# SL_LCD_SW_LED_2E.net
KiCad netlist of a schematic drawn in Altium Designer
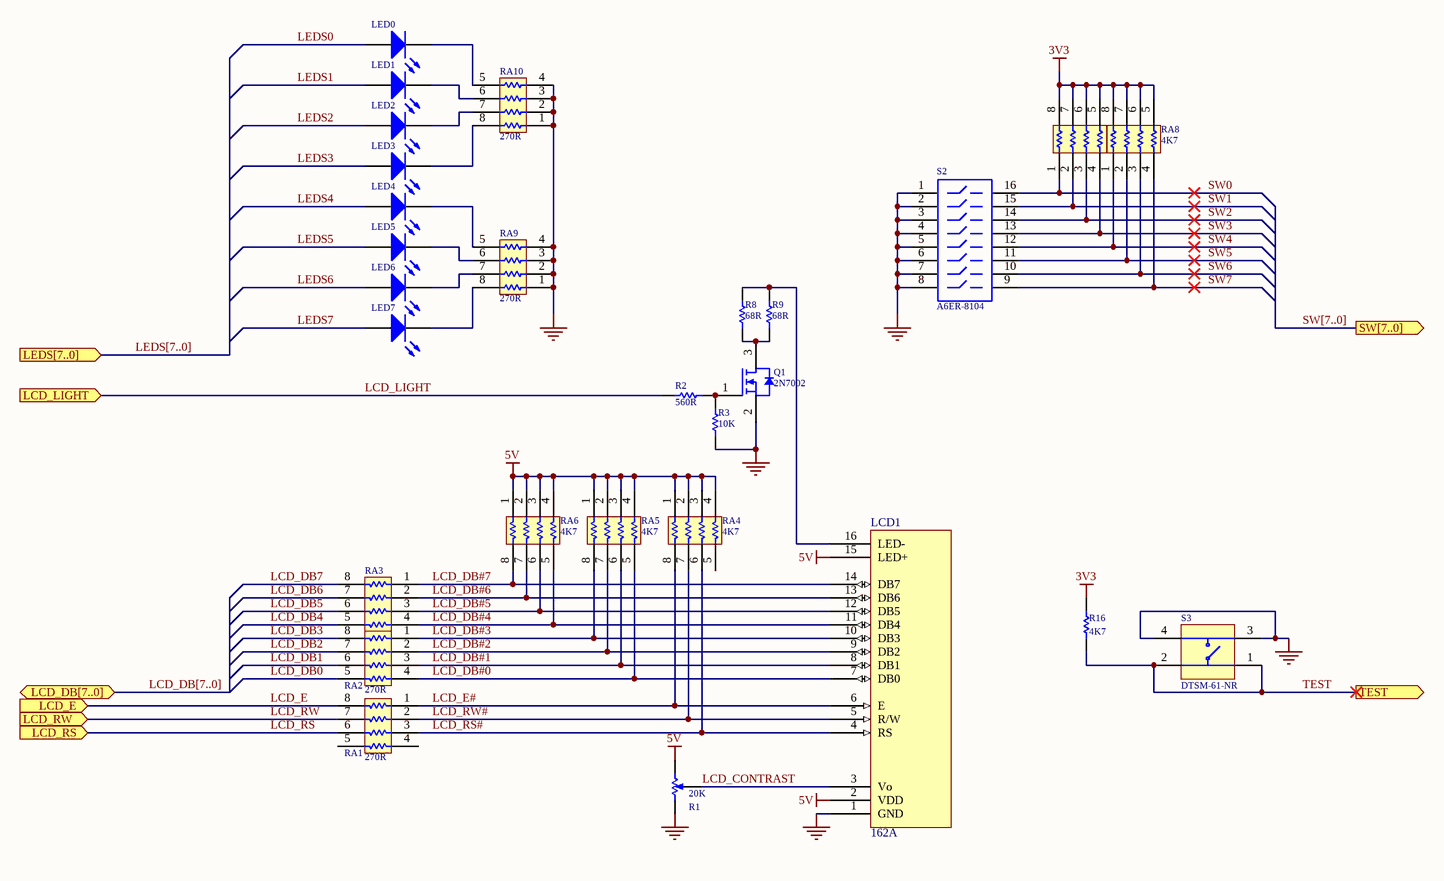
[diagram p0: SL_LCD_SW_LED_2E.SchDoc]

(export (version "E")
  (design (tool "Eeschema 10.0.6"))
  (components
    (comp (ref "LCD1")
      (value "162A")
      (footprint "Spirit_Level_Project:162A")
      (description "16 char * 2 line LCD character display with b/light")
      (libsource (lib "SpiritLevel_2E") (part "162A"))
    )
    (comp (ref "LED0")
      (value "HSMH-C170")
      (footprint "Spirit_Level_Project:SMD _LED")
      (description "Typical RED GaAs SMD LED Agilent make")
      (libsource (lib "SpiritLevel_2E") (part "HSMX-C670"))
    )
    (comp (ref "LED1")
      (value "HSMH-C170")
      (footprint "Spirit_Level_Project:SMD _LED")
      (description "Typical RED GaAs SMD LED Agilent make")
      (libsource (lib "SpiritLevel_2E") (part "HSMX-C670"))
    )
    (comp (ref "LED2")
      (value "HSMH-C170")
      (footprint "Spirit_Level_Project:SMD _LED")
      (description "Typical RED GaAs SMD LED Agilent make")
      (libsource (lib "SpiritLevel_2E") (part "HSMX-C670"))
    )
    (comp (ref "LED3")
      (value "HSMH-C170")
      (footprint "Spirit_Level_Project:SMD _LED")
      (description "Typical RED GaAs SMD LED Agilent make")
      (libsource (lib "SpiritLevel_2E") (part "HSMX-C670"))
    )
    (comp (ref "LED4")
      (value "HSMH-C170")
      (footprint "Spirit_Level_Project:SMD _LED")
      (description "Typical RED GaAs SMD LED Agilent make")
      (libsource (lib "SpiritLevel_2E") (part "HSMX-C670"))
    )
    (comp (ref "LED5")
      (value "HSMH-C170")
      (footprint "Spirit_Level_Project:SMD _LED")
      (description "Typical RED GaAs SMD LED Agilent make")
      (libsource (lib "SpiritLevel_2E") (part "HSMX-C670"))
    )
    (comp (ref "LED6")
      (value "HSMH-C170")
      (footprint "Spirit_Level_Project:SMD _LED")
      (description "Typical RED GaAs SMD LED Agilent make")
      (libsource (lib "SpiritLevel_2E") (part "HSMX-C670"))
    )
    (comp (ref "LED7")
      (value "HSMH-C170")
      (footprint "Spirit_Level_Project:SMD _LED")
      (description "Typical RED GaAs SMD LED Agilent make")
      (libsource (lib "SpiritLevel_2E") (part "HSMX-C670"))
    )
    (comp (ref "Q1")
      (value "2N7002")
      (footprint "Spirit_Level_Project:SO-G3")
      (description "N Channel Mosfet")
      (libsource (lib "SpiritLevel_2E") (part "2N7002"))
    )
    (comp (ref "R1")
      (value "20K")
      (footprint "Spirit_Level_Project:POT4MM-2")
      (description "Square Trimming Potentiometer")
      (libsource (lib "SpiritLevel_2E") (part "RPot SM"))
    )
    (comp (ref "R2")
      (value "560R")
      (footprint "CC2012-0805")
      (description "Resistor")
      (libsource (lib "SpiritLevel_2E") (part "RES"))
    )
    (comp (ref "R3")
      (value "10K")
      (footprint "CC2012-0805")
      (description "Resistor")
      (libsource (lib "SpiritLevel_2E") (part "RES"))
    )
    (comp (ref "R8")
      (value "68R")
      (footprint "CC2012-0805")
      (description "Resistor")
      (libsource (lib "") (part "RES_1"))
    )
    (comp (ref "R9")
      (value "68R")
      (footprint "CC2012-0805")
      (description "Resistor")
      (libsource (lib "") (part "RES_1"))
    )
    (comp (ref "R16")
      (value "4K7")
      (footprint "CC2012-0805")
      (description "Resistor")
      (libsource (lib "SpiritLevel_2E") (part "RES"))
    )
    (comp (ref "RA1")
      (value "270R")
      (footprint "Spirit_Level_Project:MNR34")
      (description "3216x4 Resistor Array")
      (libsource (lib "SpiritLevel_2E") (part "MNR34"))
    )
    (comp (ref "RA2")
      (value "270R")
      (footprint "Spirit_Level_Project:MNR34")
      (description "3216x4 Resistor Array")
      (libsource (lib "SpiritLevel_2E") (part "MNR34"))
    )
    (comp (ref "RA3")
      (value "270R")
      (footprint "Spirit_Level_Project:MNR34")
      (description "3216x4 Resistor Array")
      (libsource (lib "SpiritLevel_2E") (part "MNR34"))
    )
    (comp (ref "RA4")
      (value "4K7")
      (footprint "Spirit_Level_Project:MNR34T")
      (description "3216x4 Resistor Array")
      (libsource (lib "") (part "MNR34_1"))
    )
    (comp (ref "RA5")
      (value "4K7")
      (footprint "Spirit_Level_Project:MNR34T")
      (description "3216x4 Resistor Array")
      (libsource (lib "") (part "MNR34_1"))
    )
    (comp (ref "RA6")
      (value "4K7")
      (footprint "Spirit_Level_Project:MNR34T")
      (description "3216x4 Resistor Array")
      (libsource (lib "") (part "MNR34_1"))
    )
    (comp (ref "RA7")
      (value "4K7")
      (footprint "Spirit_Level_Project:MNR34T")
      (description "3216x4 Resistor Array")
      (libsource (lib "") (part "MNR34_2"))
    )
    (comp (ref "RA8")
      (value "4K7")
      (footprint "Spirit_Level_Project:MNR34T")
      (description "3216x4 Resistor Array")
      (libsource (lib "") (part "MNR34_2"))
    )
    (comp (ref "RA9")
      (value "270R")
      (footprint "Spirit_Level_Project:MNR34T")
      (description "3216x4 Resistor Array")
      (libsource (lib "") (part "MNR34_3"))
    )
    (comp (ref "RA10")
      (value "270R")
      (footprint "Spirit_Level_Project:MNR34T")
      (description "3216x4 Resistor Array")
      (libsource (lib "") (part "MNR34_3"))
    )
    (comp (ref "S2")
      (value "A6ER-8104")
      (footprint "Spirit_Level_Project:DIP-16-KEY")
      (description "DIP Switch Side actuator long liver Piano Key")
      (libsource (lib "SpiritLevel_2E") (part "A6ER-8104"))
    )
    (comp (ref "S3")
      (value "DTSM-61-NR")
      (footprint "Spirit_Level_Project:B3FS_SWITCH")
      (description "SPNA SMD Keyboard Switch")
      (libsource (lib "SpiritLevel_2E") (part "B3FS"))
    )
  )
  (nets
    (net (code "1") (name "/LCD_CONTRAST") (class "Default")
      (node (ref "LCD1") (pin "3") (pinfunction "Vo_3") (pintype "tri_state"))
      (node (ref "R1") (pin "W") (pintype "passive"))
    )
    (net (code "2") (name "/LCD_DB#0") (class "Default")
      (node (ref "LCD1") (pin "7") (pinfunction "DB0_7") (pintype "bidirectional"))
      (node (ref "RA2") (pin "4") (pintype "passive"))
      (node (ref "RA5") (pin "5") (pintype "passive"))
    )
    (net (code "3") (name "/LCD_DB#1") (class "Default")
      (node (ref "LCD1") (pin "8") (pinfunction "DB1_8") (pintype "bidirectional"))
      (node (ref "RA2") (pin "3") (pintype "passive"))
      (node (ref "RA5") (pin "6") (pintype "passive"))
    )
    (net (code "4") (name "/LCD_DB#2") (class "Default")
      (node (ref "LCD1") (pin "9") (pinfunction "DB2_9") (pintype "bidirectional"))
      (node (ref "RA2") (pin "2") (pintype "passive"))
      (node (ref "RA5") (pin "7") (pintype "passive"))
    )
    (net (code "5") (name "/LCD_DB#3") (class "Default")
      (node (ref "LCD1") (pin "10") (pinfunction "DB3_10") (pintype "bidirectional"))
      (node (ref "RA2") (pin "1") (pintype "passive"))
      (node (ref "RA5") (pin "8") (pintype "passive"))
    )
    (net (code "6") (name "/LCD_DB#4") (class "Default")
      (node (ref "LCD1") (pin "11") (pinfunction "DB4_11") (pintype "bidirectional"))
      (node (ref "RA3") (pin "4") (pintype "passive"))
      (node (ref "RA6") (pin "5") (pintype "passive"))
    )
    (net (code "7") (name "/LCD_DB#5") (class "Default")
      (node (ref "LCD1") (pin "12") (pinfunction "DB5_12") (pintype "bidirectional"))
      (node (ref "RA3") (pin "3") (pintype "passive"))
      (node (ref "RA6") (pin "6") (pintype "passive"))
    )
    (net (code "8") (name "/LCD_DB#6") (class "Default")
      (node (ref "LCD1") (pin "13") (pinfunction "DB6_13") (pintype "bidirectional"))
      (node (ref "RA3") (pin "2") (pintype "passive"))
      (node (ref "RA6") (pin "7") (pintype "passive"))
    )
    (net (code "9") (name "/LCD_DB#7") (class "Default")
      (node (ref "LCD1") (pin "14") (pinfunction "DB7_14") (pintype "bidirectional"))
      (node (ref "RA3") (pin "1") (pintype "passive"))
      (node (ref "RA6") (pin "8") (pintype "passive"))
    )
    (net (code "10") (name "/LCD_DB0") (class "Default") (node (ref "RA2") (pin "5") (pintype "passive")))
    (net (code "11") (name "/LCD_DB1") (class "Default") (node (ref "RA2") (pin "6") (pintype "passive")))
    (net (code "12") (name "/LCD_DB2") (class "Default") (node (ref "RA2") (pin "7") (pintype "passive")))
    (net (code "13") (name "/LCD_DB3") (class "Default") (node (ref "RA2") (pin "8") (pintype "passive")))
    (net (code "14") (name "/LCD_DB4") (class "Default") (node (ref "RA3") (pin "5") (pintype "passive")))
    (net (code "15") (name "/LCD_DB5") (class "Default") (node (ref "RA3") (pin "6") (pintype "passive")))
    (net (code "16") (name "/LCD_DB6") (class "Default") (node (ref "RA3") (pin "7") (pintype "passive")))
    (net (code "17") (name "/LCD_DB7") (class "Default") (node (ref "RA3") (pin "8") (pintype "passive")))
    (net (code "19") (name "/LCD_E") (class "Default") (node (ref "RA1") (pin "8") (pintype "passive")))
    (net (code "20") (name "/LCD_E#") (class "Default")
      (node (ref "LCD1") (pin "6") (pinfunction "E_6") (pintype "input"))
      (node (ref "RA1") (pin "1") (pintype "passive"))
      (node (ref "RA4") (pin "8") (pintype "passive"))
    )
    (net (code "21") (name "/LCD_LIGHT") (class "Default")
      (node (ref "R2") (pin "1") (pinfunction "1_1") (pintype "passive"))
    )
    (net (code "22") (name "/LCD_RS") (class "Default") (node (ref "RA1") (pin "6") (pintype "passive")))
    (net (code "23") (name "/LCD_RS#") (class "Default")
      (node (ref "LCD1") (pin "4") (pinfunction "RS_4") (pintype "input"))
      (node (ref "RA1") (pin "3") (pintype "passive"))
      (node (ref "RA4") (pin "6") (pintype "passive"))
    )
    (net (code "24") (name "/LCD_RW") (class "Default") (node (ref "RA1") (pin "7") (pintype "passive")))
    (net (code "25") (name "/LCD_RW#") (class "Default")
      (node (ref "LCD1") (pin "5") (pinfunction "R/W_5") (pintype "input"))
      (node (ref "RA1") (pin "2") (pintype "passive"))
      (node (ref "RA4") (pin "7") (pintype "passive"))
    )
    (net (code "26") (name "/LEDS0") (class "Default")
      (node (ref "LED0") (pin "1") (pinfunction "A_1") (pintype "passive"))
    )
    (net (code "27") (name "/LEDS1") (class "Default")
      (node (ref "LED1") (pin "1") (pinfunction "A_1") (pintype "passive"))
    )
    (net (code "28") (name "/LEDS2") (class "Default")
      (node (ref "LED2") (pin "1") (pinfunction "A_1") (pintype "passive"))
    )
    (net (code "29") (name "/LEDS3") (class "Default")
      (node (ref "LED3") (pin "1") (pinfunction "A_1") (pintype "passive"))
    )
    (net (code "30") (name "/LEDS4") (class "Default")
      (node (ref "LED4") (pin "1") (pinfunction "A_1") (pintype "passive"))
    )
    (net (code "31") (name "/LEDS5") (class "Default")
      (node (ref "LED5") (pin "1") (pinfunction "A_1") (pintype "passive"))
    )
    (net (code "32") (name "/LEDS6") (class "Default")
      (node (ref "LED6") (pin "1") (pinfunction "A_1") (pintype "passive"))
    )
    (net (code "33") (name "/LEDS7") (class "Default")
      (node (ref "LED7") (pin "1") (pinfunction "A_1") (pintype "passive"))
    )
    (net (code "35") (name "/SW0") (class "Default")
      (node (ref "RA7") (pin "1") (pintype "passive"))
      (node (ref "S2") (pin "16") (pinfunction "16_16") (pintype "passive"))
    )
    (net (code "36") (name "/SW1") (class "Default")
      (node (ref "RA7") (pin "2") (pintype "passive"))
      (node (ref "S2") (pin "15") (pinfunction "15_15") (pintype "passive"))
    )
    (net (code "37") (name "/SW2") (class "Default")
      (node (ref "RA7") (pin "3") (pintype "passive"))
      (node (ref "S2") (pin "14") (pinfunction "14_14") (pintype "passive"))
    )
    (net (code "38") (name "/SW3") (class "Default")
      (node (ref "RA7") (pin "4") (pintype "passive"))
      (node (ref "S2") (pin "13") (pinfunction "13_13") (pintype "passive"))
    )
    (net (code "39") (name "/SW4") (class "Default")
      (node (ref "RA8") (pin "1") (pintype "passive"))
      (node (ref "S2") (pin "12") (pinfunction "12_12") (pintype "passive"))
    )
    (net (code "40") (name "/SW5") (class "Default")
      (node (ref "RA8") (pin "2") (pintype "passive"))
      (node (ref "S2") (pin "11") (pinfunction "11_11") (pintype "passive"))
    )
    (net (code "41") (name "/SW6") (class "Default")
      (node (ref "RA8") (pin "3") (pintype "passive"))
      (node (ref "S2") (pin "10") (pinfunction "10_10") (pintype "passive"))
    )
    (net (code "42") (name "/SW7") (class "Default")
      (node (ref "RA8") (pin "4") (pintype "passive"))
      (node (ref "S2") (pin "9") (pinfunction "9_9") (pintype "passive"))
    )
    (net (code "44") (name "/TEST") (class "Default")
      (node (ref "R16") (pin "2") (pinfunction "2_2") (pintype "passive"))
      (node (ref "S3") (pin "1") (pinfunction "1_1") (pintype "passive"))
      (node (ref "S3") (pin "2") (pinfunction "2_2") (pintype "passive"))
    )
    (net (code "45") (name "3V3") (class "Default")
      (node (ref "R16") (pin "1") (pinfunction "1_1") (pintype "passive"))
      (node (ref "RA7") (pin "5") (pintype "passive"))
      (node (ref "RA7") (pin "6") (pintype "passive"))
      (node (ref "RA7") (pin "7") (pintype "passive"))
      (node (ref "RA7") (pin "8") (pintype "passive"))
      (node (ref "RA8") (pin "5") (pintype "passive"))
      (node (ref "RA8") (pin "6") (pintype "passive"))
      (node (ref "RA8") (pin "7") (pintype "passive"))
      (node (ref "RA8") (pin "8") (pintype "passive"))
    )
    (net (code "46") (name "5V") (class "Default")
      (node (ref "LCD1") (pin "15") (pinfunction "LED+_15") (pintype "power_in"))
      (node (ref "LCD1") (pin "2") (pinfunction "VDD_2") (pintype "power_in"))
      (node (ref "R1") (pin "CW") (pinfunction "+_CW") (pintype "passive"))
      (node (ref "RA4") (pin "1") (pintype "passive"))
      (node (ref "RA4") (pin "2") (pintype "passive"))
      (node (ref "RA4") (pin "3") (pintype "passive"))
      (node (ref "RA4") (pin "4") (pintype "passive"))
      (node (ref "RA5") (pin "1") (pintype "passive"))
      (node (ref "RA5") (pin "2") (pintype "passive"))
      (node (ref "RA5") (pin "3") (pintype "passive"))
      (node (ref "RA5") (pin "4") (pintype "passive"))
      (node (ref "RA6") (pin "1") (pintype "passive"))
      (node (ref "RA6") (pin "2") (pintype "passive"))
      (node (ref "RA6") (pin "3") (pintype "passive"))
      (node (ref "RA6") (pin "4") (pintype "passive"))
    )
    (net (code "47") (name "GND") (class "Default")
      (node (ref "LCD1") (pin "1") (pinfunction "GND_1") (pintype "power_in"))
      (node (ref "Q1") (pin "2") (pintype "passive"))
      (node (ref "R1") (pin "CCW") (pinfunction "-_CCW") (pintype "passive"))
      (node (ref "R3") (pin "1") (pinfunction "1_1") (pintype "passive"))
      (node (ref "RA10") (pin "1") (pintype "passive"))
      (node (ref "RA10") (pin "2") (pintype "passive"))
      (node (ref "RA10") (pin "3") (pintype "passive"))
      (node (ref "RA10") (pin "4") (pintype "passive"))
      (node (ref "RA9") (pin "1") (pintype "passive"))
      (node (ref "RA9") (pin "2") (pintype "passive"))
      (node (ref "RA9") (pin "3") (pintype "passive"))
      (node (ref "RA9") (pin "4") (pintype "passive"))
      (node (ref "S2") (pin "1") (pinfunction "1_1") (pintype "passive"))
      (node (ref "S2") (pin "2") (pinfunction "2_2") (pintype "passive"))
      (node (ref "S2") (pin "3") (pinfunction "3_3") (pintype "passive"))
      (node (ref "S2") (pin "4") (pinfunction "4_4") (pintype "passive"))
      (node (ref "S2") (pin "5") (pinfunction "5_5") (pintype "passive"))
      (node (ref "S2") (pin "6") (pinfunction "6_6") (pintype "passive"))
      (node (ref "S2") (pin "7") (pinfunction "7_7") (pintype "passive"))
      (node (ref "S2") (pin "8") (pinfunction "8_8") (pintype "passive"))
      (node (ref "S3") (pin "3") (pinfunction "3_3") (pintype "passive"))
      (node (ref "S3") (pin "4") (pinfunction "4_4") (pintype "passive"))
    )
    (net (code "48") (name "Net-(LCD1-LED-)") (class "Default")
      (node (ref "LCD1") (pin "16") (pinfunction "LED-_16") (pintype "power_in"))
      (node (ref "R8") (pin "1") (pinfunction "1_1") (pintype "passive"))
      (node (ref "R9") (pin "1") (pinfunction "1_1") (pintype "passive"))
    )
    (net (code "49") (name "Net-(LED0-K)") (class "Default")
      (node (ref "LED0") (pin "2") (pinfunction "K_2") (pintype "passive"))
      (node (ref "RA10") (pin "5") (pintype "passive"))
    )
    (net (code "50") (name "Net-(LED1-K)") (class "Default")
      (node (ref "LED1") (pin "2") (pinfunction "K_2") (pintype "passive"))
      (node (ref "RA10") (pin "6") (pintype "passive"))
    )
    (net (code "51") (name "Net-(LED2-K)") (class "Default")
      (node (ref "LED2") (pin "2") (pinfunction "K_2") (pintype "passive"))
      (node (ref "RA10") (pin "7") (pintype "passive"))
    )
    (net (code "52") (name "Net-(LED3-K)") (class "Default")
      (node (ref "LED3") (pin "2") (pinfunction "K_2") (pintype "passive"))
      (node (ref "RA10") (pin "8") (pintype "passive"))
    )
    (net (code "53") (name "Net-(LED4-K)") (class "Default")
      (node (ref "LED4") (pin "2") (pinfunction "K_2") (pintype "passive"))
      (node (ref "RA9") (pin "5") (pintype "passive"))
    )
    (net (code "54") (name "Net-(LED5-K)") (class "Default")
      (node (ref "LED5") (pin "2") (pinfunction "K_2") (pintype "passive"))
      (node (ref "RA9") (pin "6") (pintype "passive"))
    )
    (net (code "55") (name "Net-(LED6-K)") (class "Default")
      (node (ref "LED6") (pin "2") (pinfunction "K_2") (pintype "passive"))
      (node (ref "RA9") (pin "7") (pintype "passive"))
    )
    (net (code "56") (name "Net-(LED7-K)") (class "Default")
      (node (ref "LED7") (pin "2") (pinfunction "K_2") (pintype "passive"))
      (node (ref "RA9") (pin "8") (pintype "passive"))
    )
    (net (code "57") (name "Net-(Q1-Pad1)") (class "Default")
      (node (ref "Q1") (pin "1") (pintype "passive"))
      (node (ref "R2") (pin "2") (pinfunction "2_2") (pintype "passive"))
      (node (ref "R3") (pin "2") (pinfunction "2_2") (pintype "passive"))
    )
    (net (code "58") (name "Net-(Q1-Pad3)") (class "Default")
      (node (ref "Q1") (pin "3") (pintype "passive"))
      (node (ref "R8") (pin "2") (pinfunction "2_2") (pintype "passive"))
      (node (ref "R9") (pin "2") (pinfunction "2_2") (pintype "passive"))
    )
    (net (code "59") (name "unconnected-(RA1-Pad4)") (class "Default")
      (node (ref "RA1") (pin "4") (pintype "passive"))
    )
    (net (code "60") (name "unconnected-(RA1-Pad5)") (class "Default")
      (node (ref "RA1") (pin "5") (pintype "passive"))
    )
    (net (code "61") (name "unconnected-(RA4-Pad5)") (class "Default")
      (node (ref "RA4") (pin "5") (pintype "passive"))
    )
  )
)
